# motor_ic.net
KiCad netlist of a schematic drawn in EAGLE
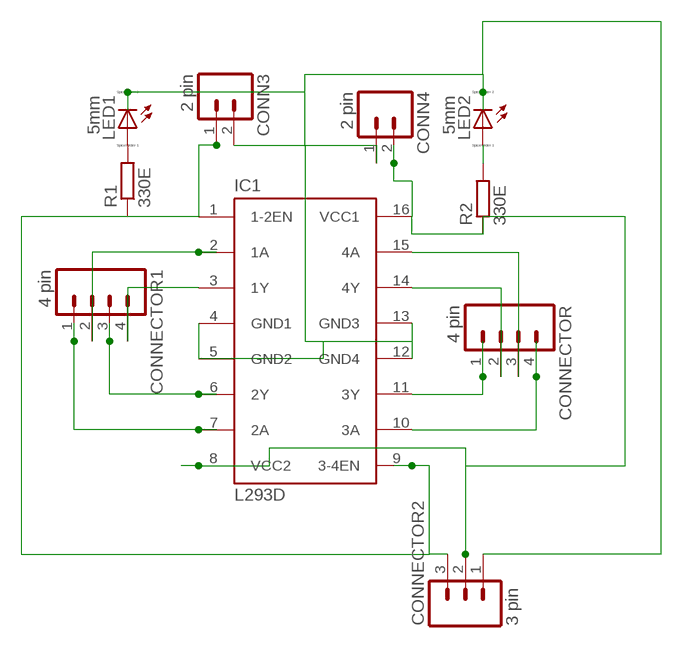
[diagram p0: schematic, sheet 1]

(export (version "E")
  (design (tool "Eeschema 10.0.6"))
  (components
    (comp (ref "CONN3")
      (value "2 pin")
      (footprint "eagle-import:02P")
      (libsource (lib "eagle-import") (part "M02"))
    )
    (comp (ref "CONN4")
      (value "2 pin")
      (footprint "eagle-import:02P")
      (libsource (lib "eagle-import") (part "M02"))
    )
    (comp (ref "CONNECTOR")
      (value "4 pin")
      (footprint "eagle-import:04P")
      (libsource (lib "eagle-import") (part "M04"))
    )
    (comp (ref "CONNECTOR1")
      (value "4 pin")
      (footprint "eagle-import:04P")
      (libsource (lib "eagle-import") (part "M04"))
    )
    (comp (ref "CONNECTOR2")
      (value "3 pin")
      (footprint "eagle-import:03P")
      (libsource (lib "eagle-import") (part "M03"))
    )
    (comp (ref "IC1")
      (value "L293D")
      (footprint "eagle-import:DIL16")
      (libsource (lib "eagle-import") (part "L293D"))
    )
    (comp (ref "LED1")
      (value "5mm")
      (footprint "eagle-import:LED_LD260")
      (libsource (lib "eagle-import") (part "LED_ELD260"))
    )
    (comp (ref "LED2")
      (value "5mm")
      (footprint "eagle-import:LED_LD260")
      (libsource (lib "eagle-import") (part "LED_ELD260"))
    )
    (comp (ref "R1")
      (value "330E")
      (footprint "eagle-import:0204_7")
      (libsource (lib "eagle-import") (part "R-EU_0204/7"))
    )
    (comp (ref "R2")
      (value "330E")
      (footprint "eagle-import:0204_7")
      (libsource (lib "eagle-import") (part "R-EU_0204/7"))
    )
  )
  (nets
    (net (code "1") (name "Net-(IC1-1-2EN)") (class "Default")
      (node (ref "CONN3") (pin "1") (pinfunction "1_1") (pintype "passive"))
      (node (ref "CONNECTOR2") (pin "3") (pinfunction "3_3") (pintype "passive"))
      (node (ref "IC1") (pin "1") (pinfunction "1-2EN_1") (pintype "input"))
      (node (ref "IC1") (pin "9") (pinfunction "3-4EN_9") (pintype "input"))
      (node (ref "R1") (pin "1") (pinfunction "1_1") (pintype "passive"))
    )
    (net (code "2") (name "Net-(IC1-1A)") (class "Default")
      (node (ref "CONNECTOR1") (pin "2") (pinfunction "2_2") (pintype "passive"))
      (node (ref "IC1") (pin "2") (pinfunction "1A_2") (pintype "input"))
    )
    (net (code "3") (name "Net-(IC1-1Y)") (class "Default")
      (node (ref "CONNECTOR1") (pin "4") (pinfunction "4_4") (pintype "passive"))
      (node (ref "IC1") (pin "3") (pinfunction "1Y_3") (pintype "output"))
    )
    (net (code "4") (name "Net-(IC1-2A)") (class "Default")
      (node (ref "CONNECTOR1") (pin "1") (pinfunction "1_1") (pintype "passive"))
      (node (ref "IC1") (pin "7") (pinfunction "2A_7") (pintype "input"))
    )
    (net (code "5") (name "Net-(IC1-2Y)") (class "Default")
      (node (ref "CONNECTOR1") (pin "3") (pinfunction "3_3") (pintype "passive"))
      (node (ref "IC1") (pin "6") (pinfunction "2Y_6") (pintype "output"))
    )
    (net (code "6") (name "Net-(IC1-3A)") (class "Default")
      (node (ref "CONNECTOR") (pin "4") (pinfunction "4_4") (pintype "passive"))
      (node (ref "IC1") (pin "10") (pinfunction "3A_10") (pintype "input"))
    )
    (net (code "7") (name "Net-(IC1-3Y)") (class "Default")
      (node (ref "CONNECTOR") (pin "1") (pinfunction "1_1") (pintype "passive"))
      (node (ref "IC1") (pin "11") (pinfunction "3Y_11") (pintype "output"))
    )
    (net (code "8") (name "Net-(IC1-4A)") (class "Default")
      (node (ref "CONNECTOR") (pin "3") (pinfunction "3_3") (pintype "passive"))
      (node (ref "IC1") (pin "15") (pinfunction "4A_15") (pintype "input"))
    )
    (net (code "9") (name "Net-(IC1-4Y)") (class "Default")
      (node (ref "CONNECTOR") (pin "2") (pinfunction "2_2") (pintype "passive"))
      (node (ref "IC1") (pin "14") (pinfunction "4Y_14") (pintype "output"))
    )
    (net (code "10") (name "Net-(IC1-GND1)") (class "Default")
      (node (ref "CONN3") (pin "2") (pinfunction "2_2") (pintype "passive"))
      (node (ref "CONN4") (pin "1") (pinfunction "1_1") (pintype "passive"))
      (node (ref "CONNECTOR2") (pin "1") (pinfunction "1_1") (pintype "passive"))
      (node (ref "IC1") (pin "12") (pinfunction "GND4_12") (pintype "power_in"))
      (node (ref "IC1") (pin "13") (pinfunction "GND3_13") (pintype "power_in"))
      (node (ref "IC1") (pin "4") (pinfunction "GND1_4") (pintype "power_in"))
      (node (ref "IC1") (pin "5") (pinfunction "GND2_5") (pintype "power_in"))
      (node (ref "LED1") (pin "K") (pinfunction "C_K") (pintype "passive"))
      (node (ref "LED2") (pin "K") (pinfunction "C_K") (pintype "passive"))
    )
    (net (code "11") (name "Net-(IC1-VCC1)") (class "Default")
      (node (ref "CONN4") (pin "2") (pinfunction "2_2") (pintype "passive"))
      (node (ref "CONNECTOR2") (pin "2") (pinfunction "2_2") (pintype "passive"))
      (node (ref "IC1") (pin "16") (pinfunction "VCC1_16") (pintype "power_in"))
      (node (ref "IC1") (pin "8") (pinfunction "VCC2_8") (pintype "power_in"))
      (node (ref "R2") (pin "1") (pinfunction "1_1") (pintype "passive"))
    )
    (net (code "12") (name "Net-(LED1-PadA)") (class "Default")
      (node (ref "LED1") (pin "A") (pinfunction "A_A") (pintype "passive"))
      (node (ref "R1") (pin "2") (pinfunction "2_2") (pintype "passive"))
    )
    (net (code "13") (name "Net-(LED2-PadA)") (class "Default")
      (node (ref "LED2") (pin "A") (pinfunction "A_A") (pintype "passive"))
      (node (ref "R2") (pin "2") (pinfunction "2_2") (pintype "passive"))
    )
  )
)
